# VIC_proto.net
KiCad netlist of a schematic drawn in EAGLE
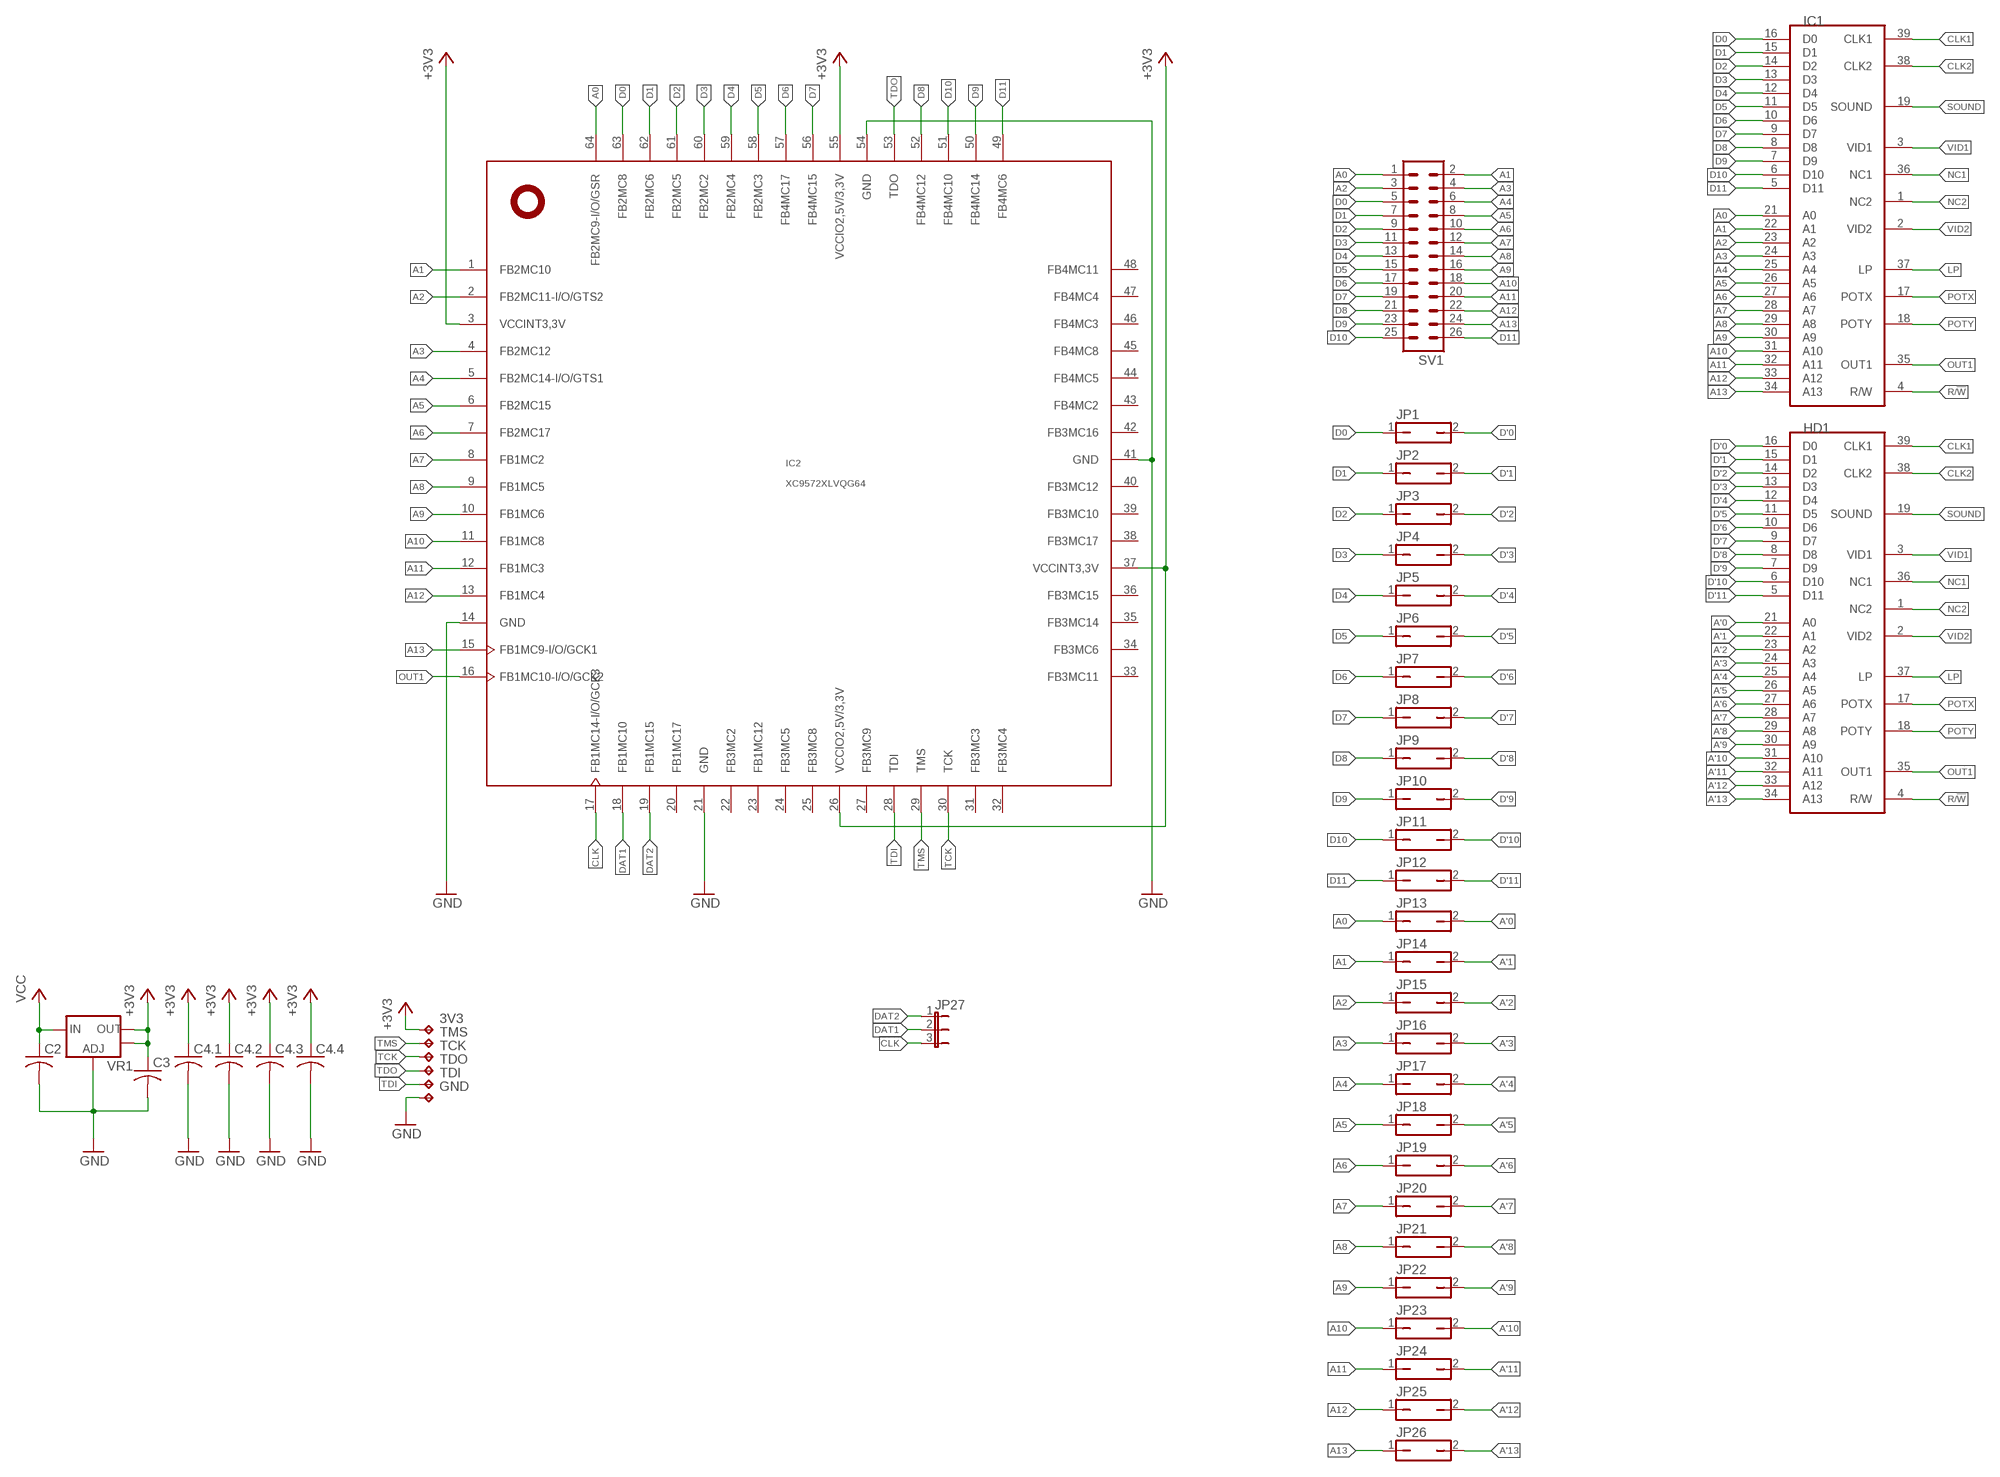
[diagram p0: schematic, sheet 1]

(export (version "E")
  (design (tool "Eeschema 10.0.6"))
  (components
    (comp (ref "3V3")
      (value "TPTP09R")
      (footprint "eagle-import:TP09R")
      (libsource (lib "eagle-import") (part "TPTP09R"))
    )
    (comp (ref "C2")
      (value "C-USC0805")
      (footprint "eagle-import:C0805")
      (libsource (lib "eagle-import") (part "C-USC0805"))
    )
    (comp (ref "C3")
      (value "C-USC0805")
      (footprint "eagle-import:C0805")
      (libsource (lib "eagle-import") (part "C-USC0805"))
    )
    (comp (ref "C4.1")
      (value "C-USC0402")
      (footprint "eagle-import:C0402")
      (libsource (lib "eagle-import") (part "C-USC0402"))
    )
    (comp (ref "C4.2")
      (value "C-USC0402")
      (footprint "eagle-import:C0402")
      (libsource (lib "eagle-import") (part "C-USC0402"))
    )
    (comp (ref "C4.3")
      (value "C-USC0402")
      (footprint "eagle-import:C0402")
      (libsource (lib "eagle-import") (part "C-USC0402"))
    )
    (comp (ref "C4.4")
      (value "C-USC0402")
      (footprint "eagle-import:C0402")
      (libsource (lib "eagle-import") (part "C-USC0402"))
    )
    (comp (ref "GND")
      (value "TPTP10R")
      (footprint "eagle-import:TP10R")
      (libsource (lib "eagle-import") (part "TPTP10R"))
    )
    (comp (ref "HD1")
      (value "6560-RP")
      (footprint "eagle-import:DIL40-ROUNDPAD")
      (libsource (lib "eagle-import") (part "6560-RP"))
    )
    (comp (ref "IC1")
      (value "6560-RP")
      (footprint "eagle-import:DIL40-ROUNDPAD")
      (libsource (lib "eagle-import") (part "6560-RP"))
    )
    (comp (ref "IC2")
      (value "XC9572XLVQG64")
      (footprint "eagle-import:VQFP64")
      (libsource (lib "eagle-import") (part "XC9572XLVQG64"))
    )
    (comp (ref "JP1")
      (value "JP1Q")
      (footprint "eagle-import:JP1")
      (libsource (lib "eagle-import") (part "JP1Q"))
    )
    (comp (ref "JP2")
      (value "JP1Q")
      (footprint "eagle-import:JP1")
      (libsource (lib "eagle-import") (part "JP1Q"))
    )
    (comp (ref "JP3")
      (value "JP1Q")
      (footprint "eagle-import:JP1")
      (libsource (lib "eagle-import") (part "JP1Q"))
    )
    (comp (ref "JP4")
      (value "JP1Q")
      (footprint "eagle-import:JP1")
      (libsource (lib "eagle-import") (part "JP1Q"))
    )
    (comp (ref "JP5")
      (value "JP1Q")
      (footprint "eagle-import:JP1")
      (libsource (lib "eagle-import") (part "JP1Q"))
    )
    (comp (ref "JP6")
      (value "JP1Q")
      (footprint "eagle-import:JP1")
      (libsource (lib "eagle-import") (part "JP1Q"))
    )
    (comp (ref "JP7")
      (value "JP1Q")
      (footprint "eagle-import:JP1")
      (libsource (lib "eagle-import") (part "JP1Q"))
    )
    (comp (ref "JP8")
      (value "JP1Q")
      (footprint "eagle-import:JP1")
      (libsource (lib "eagle-import") (part "JP1Q"))
    )
    (comp (ref "JP9")
      (value "JP1Q")
      (footprint "eagle-import:JP1")
      (libsource (lib "eagle-import") (part "JP1Q"))
    )
    (comp (ref "JP10")
      (value "JP1Q")
      (footprint "eagle-import:JP1")
      (libsource (lib "eagle-import") (part "JP1Q"))
    )
    (comp (ref "JP11")
      (value "JP1Q")
      (footprint "eagle-import:JP1")
      (libsource (lib "eagle-import") (part "JP1Q"))
    )
    (comp (ref "JP12")
      (value "JP1Q")
      (footprint "eagle-import:JP1")
      (libsource (lib "eagle-import") (part "JP1Q"))
    )
    (comp (ref "JP13")
      (value "JP1Q")
      (footprint "eagle-import:JP1")
      (libsource (lib "eagle-import") (part "JP1Q"))
    )
    (comp (ref "JP14")
      (value "JP1Q")
      (footprint "eagle-import:JP1")
      (libsource (lib "eagle-import") (part "JP1Q"))
    )
    (comp (ref "JP15")
      (value "JP1Q")
      (footprint "eagle-import:JP1")
      (libsource (lib "eagle-import") (part "JP1Q"))
    )
    (comp (ref "JP16")
      (value "JP1Q")
      (footprint "eagle-import:JP1")
      (libsource (lib "eagle-import") (part "JP1Q"))
    )
    (comp (ref "JP17")
      (value "JP1Q")
      (footprint "eagle-import:JP1")
      (libsource (lib "eagle-import") (part "JP1Q"))
    )
    (comp (ref "JP18")
      (value "JP1Q")
      (footprint "eagle-import:JP1")
      (libsource (lib "eagle-import") (part "JP1Q"))
    )
    (comp (ref "JP19")
      (value "JP1Q")
      (footprint "eagle-import:JP1")
      (libsource (lib "eagle-import") (part "JP1Q"))
    )
    (comp (ref "JP20")
      (value "JP1Q")
      (footprint "eagle-import:JP1")
      (libsource (lib "eagle-import") (part "JP1Q"))
    )
    (comp (ref "JP21")
      (value "JP1Q")
      (footprint "eagle-import:JP1")
      (libsource (lib "eagle-import") (part "JP1Q"))
    )
    (comp (ref "JP22")
      (value "JP1Q")
      (footprint "eagle-import:JP1")
      (libsource (lib "eagle-import") (part "JP1Q"))
    )
    (comp (ref "JP23")
      (value "JP1Q")
      (footprint "eagle-import:JP1")
      (libsource (lib "eagle-import") (part "JP1Q"))
    )
    (comp (ref "JP24")
      (value "JP1Q")
      (footprint "eagle-import:JP1")
      (libsource (lib "eagle-import") (part "JP1Q"))
    )
    (comp (ref "JP25")
      (value "JP1Q")
      (footprint "eagle-import:JP1")
      (libsource (lib "eagle-import") (part "JP1Q"))
    )
    (comp (ref "JP26")
      (value "JP1Q")
      (footprint "eagle-import:JP1")
      (libsource (lib "eagle-import") (part "JP1Q"))
    )
    (comp (ref "JP27")
      (value "JP2E")
      (footprint "eagle-import:JP2")
      (libsource (lib "eagle-import") (part "JP2E"))
    )
    (comp (ref "SV1")
      (value "MA13-2")
      (footprint "eagle-import:MA13-2")
      (libsource (lib "eagle-import") (part "MA13-2"))
    )
    (comp (ref "TCK")
      (value "TPTP09R")
      (footprint "eagle-import:TP09R")
      (libsource (lib "eagle-import") (part "TPTP09R"))
    )
    (comp (ref "TDI")
      (value "TPTP09R")
      (footprint "eagle-import:TP09R")
      (libsource (lib "eagle-import") (part "TPTP09R"))
    )
    (comp (ref "TDO")
      (value "TPTP09R")
      (footprint "eagle-import:TP09R")
      (libsource (lib "eagle-import") (part "TPTP09R"))
    )
    (comp (ref "TMS")
      (value "TPTP09R")
      (footprint "eagle-import:TP09R")
      (libsource (lib "eagle-import") (part "TPTP09R"))
    )
    (comp (ref "VR1")
      (value "V_REG_LM1117SOT223")
      (footprint "eagle-import:SOT223")
      (libsource (lib "eagle-import") (part "V_REG_LM1117SOT223"))
    )
  )
  (nets
    (net (code "1") (name "+3V3") (class "Default")
      (node (ref "3V3") (pin "TP") (pinfunction "TP_TP") (pintype "input"))
      (node (ref "C3") (pin "1") (pinfunction "1_1") (pintype "passive"))
      (node (ref "C4.1") (pin "1") (pinfunction "1_1") (pintype "passive"))
      (node (ref "C4.2") (pin "1") (pinfunction "1_1") (pintype "passive"))
      (node (ref "C4.3") (pin "1") (pinfunction "1_1") (pintype "passive"))
      (node (ref "C4.4") (pin "1") (pinfunction "1_1") (pintype "passive"))
      (node (ref "IC2") (pin "26") (pinfunction "VCCIO2,5V/3,3V_26") (pintype "power_in"))
      (node (ref "IC2") (pin "3") (pinfunction "VCCINT3,3V_3") (pintype "power_in"))
      (node (ref "IC2") (pin "37") (pinfunction "VCCINT3,3V_37") (pintype "power_in"))
      (node (ref "IC2") (pin "55") (pinfunction "VCCIO2,5V/3,3V_55") (pintype "power_in"))
      (node (ref "VR1") (pin "2") (pinfunction "OUT_2") (pintype "output"))
      (node (ref "VR1") (pin "4") (pinfunction "OUT_4") (pintype "output"))
    )
    (net (code "2") (name "/R{slash}~{W}") (class "Default")
      (node (ref "HD1") (pin "4") (pinfunction "R/W_4") (pintype "input"))
      (node (ref "IC1") (pin "4") (pinfunction "R/W_4") (pintype "input"))
    )
    (net (code "3") (name "A'0") (class "Default")
      (node (ref "HD1") (pin "21") (pinfunction "A0_21") (pintype "bidirectional"))
      (node (ref "JP13") (pin "2") (pinfunction "2_2") (pintype "passive"))
    )
    (net (code "4") (name "A'1") (class "Default")
      (node (ref "HD1") (pin "22") (pinfunction "A1_22") (pintype "bidirectional"))
      (node (ref "JP14") (pin "2") (pinfunction "2_2") (pintype "passive"))
    )
    (net (code "5") (name "A'2") (class "Default")
      (node (ref "HD1") (pin "23") (pinfunction "A2_23") (pintype "bidirectional"))
      (node (ref "JP15") (pin "2") (pinfunction "2_2") (pintype "passive"))
    )
    (net (code "6") (name "A'3") (class "Default")
      (node (ref "HD1") (pin "24") (pinfunction "A3_24") (pintype "bidirectional"))
      (node (ref "JP16") (pin "2") (pinfunction "2_2") (pintype "passive"))
    )
    (net (code "7") (name "A'4") (class "Default")
      (node (ref "HD1") (pin "25") (pinfunction "A4_25") (pintype "bidirectional"))
      (node (ref "JP17") (pin "2") (pinfunction "2_2") (pintype "passive"))
    )
    (net (code "8") (name "A'5") (class "Default")
      (node (ref "HD1") (pin "26") (pinfunction "A5_26") (pintype "bidirectional"))
      (node (ref "JP18") (pin "2") (pinfunction "2_2") (pintype "passive"))
    )
    (net (code "9") (name "A'6") (class "Default")
      (node (ref "HD1") (pin "27") (pinfunction "A6_27") (pintype "bidirectional"))
      (node (ref "JP19") (pin "2") (pinfunction "2_2") (pintype "passive"))
    )
    (net (code "10") (name "A'7") (class "Default")
      (node (ref "HD1") (pin "28") (pinfunction "A7_28") (pintype "bidirectional"))
      (node (ref "JP20") (pin "2") (pinfunction "2_2") (pintype "passive"))
    )
    (net (code "11") (name "A'8") (class "Default")
      (node (ref "HD1") (pin "29") (pinfunction "A8_29") (pintype "bidirectional"))
      (node (ref "JP21") (pin "2") (pinfunction "2_2") (pintype "passive"))
    )
    (net (code "12") (name "A'9") (class "Default")
      (node (ref "HD1") (pin "30") (pinfunction "A9_30") (pintype "bidirectional"))
      (node (ref "JP22") (pin "2") (pinfunction "2_2") (pintype "passive"))
    )
    (net (code "13") (name "A'10") (class "Default")
      (node (ref "HD1") (pin "31") (pinfunction "A10_31") (pintype "bidirectional"))
      (node (ref "JP23") (pin "2") (pinfunction "2_2") (pintype "passive"))
    )
    (net (code "14") (name "A'11") (class "Default")
      (node (ref "HD1") (pin "32") (pinfunction "A11_32") (pintype "bidirectional"))
      (node (ref "JP24") (pin "2") (pinfunction "2_2") (pintype "passive"))
    )
    (net (code "15") (name "A'12") (class "Default")
      (node (ref "HD1") (pin "33") (pinfunction "A12_33") (pintype "bidirectional"))
      (node (ref "JP25") (pin "2") (pinfunction "2_2") (pintype "passive"))
    )
    (net (code "16") (name "A'13") (class "Default")
      (node (ref "HD1") (pin "34") (pinfunction "A13_34") (pintype "bidirectional"))
      (node (ref "JP26") (pin "2") (pinfunction "2_2") (pintype "passive"))
    )
    (net (code "17") (name "A0") (class "Default")
      (node (ref "IC1") (pin "21") (pinfunction "A0_21") (pintype "bidirectional"))
      (node (ref "IC2") (pin "64") (pinfunction "FB2MC9-I/O/GSR_64") (pintype "bidirectional"))
      (node (ref "JP13") (pin "1") (pinfunction "1_1") (pintype "passive"))
      (node (ref "SV1") (pin "1") (pinfunction "1_1") (pintype "passive"))
    )
    (net (code "18") (name "A1") (class "Default")
      (node (ref "IC1") (pin "22") (pinfunction "A1_22") (pintype "bidirectional"))
      (node (ref "IC2") (pin "1") (pinfunction "FB2MC10_1") (pintype "bidirectional"))
      (node (ref "JP14") (pin "1") (pinfunction "1_1") (pintype "passive"))
      (node (ref "SV1") (pin "2") (pinfunction "2_2") (pintype "passive"))
    )
    (net (code "19") (name "A2") (class "Default")
      (node (ref "IC1") (pin "23") (pinfunction "A2_23") (pintype "bidirectional"))
      (node (ref "IC2") (pin "2") (pinfunction "FB2MC11-I/O/GTS2_2") (pintype "bidirectional"))
      (node (ref "JP15") (pin "1") (pinfunction "1_1") (pintype "passive"))
      (node (ref "SV1") (pin "3") (pinfunction "3_3") (pintype "passive"))
    )
    (net (code "20") (name "A3") (class "Default")
      (node (ref "IC1") (pin "24") (pinfunction "A3_24") (pintype "bidirectional"))
      (node (ref "IC2") (pin "4") (pinfunction "FB2MC12_4") (pintype "bidirectional"))
      (node (ref "JP16") (pin "1") (pinfunction "1_1") (pintype "passive"))
      (node (ref "SV1") (pin "4") (pinfunction "4_4") (pintype "passive"))
    )
    (net (code "21") (name "A4") (class "Default")
      (node (ref "IC1") (pin "25") (pinfunction "A4_25") (pintype "bidirectional"))
      (node (ref "IC2") (pin "5") (pinfunction "FB2MC14-I/O/GTS1_5") (pintype "bidirectional"))
      (node (ref "JP17") (pin "1") (pinfunction "1_1") (pintype "passive"))
      (node (ref "SV1") (pin "6") (pinfunction "6_6") (pintype "passive"))
    )
    (net (code "22") (name "A5") (class "Default")
      (node (ref "IC1") (pin "26") (pinfunction "A5_26") (pintype "bidirectional"))
      (node (ref "IC2") (pin "6") (pinfunction "FB2MC15_6") (pintype "bidirectional"))
      (node (ref "JP18") (pin "1") (pinfunction "1_1") (pintype "passive"))
      (node (ref "SV1") (pin "8") (pinfunction "8_8") (pintype "passive"))
    )
    (net (code "23") (name "A6") (class "Default")
      (node (ref "IC1") (pin "27") (pinfunction "A6_27") (pintype "bidirectional"))
      (node (ref "IC2") (pin "7") (pinfunction "FB2MC17_7") (pintype "bidirectional"))
      (node (ref "JP19") (pin "1") (pinfunction "1_1") (pintype "passive"))
      (node (ref "SV1") (pin "10") (pinfunction "10_10") (pintype "passive"))
    )
    (net (code "24") (name "A7") (class "Default")
      (node (ref "IC1") (pin "28") (pinfunction "A7_28") (pintype "bidirectional"))
      (node (ref "IC2") (pin "8") (pinfunction "FB1MC2_8") (pintype "bidirectional"))
      (node (ref "JP20") (pin "1") (pinfunction "1_1") (pintype "passive"))
      (node (ref "SV1") (pin "12") (pinfunction "12_12") (pintype "passive"))
    )
    (net (code "25") (name "A8") (class "Default")
      (node (ref "IC1") (pin "29") (pinfunction "A8_29") (pintype "bidirectional"))
      (node (ref "IC2") (pin "9") (pinfunction "FB1MC5_9") (pintype "bidirectional"))
      (node (ref "JP21") (pin "1") (pinfunction "1_1") (pintype "passive"))
      (node (ref "SV1") (pin "14") (pinfunction "14_14") (pintype "passive"))
    )
    (net (code "26") (name "A9") (class "Default")
      (node (ref "IC1") (pin "30") (pinfunction "A9_30") (pintype "bidirectional"))
      (node (ref "IC2") (pin "10") (pinfunction "FB1MC6_10") (pintype "bidirectional"))
      (node (ref "JP22") (pin "1") (pinfunction "1_1") (pintype "passive"))
      (node (ref "SV1") (pin "16") (pinfunction "16_16") (pintype "passive"))
    )
    (net (code "27") (name "A10") (class "Default")
      (node (ref "IC1") (pin "31") (pinfunction "A10_31") (pintype "bidirectional"))
      (node (ref "IC2") (pin "11") (pinfunction "FB1MC8_11") (pintype "bidirectional"))
      (node (ref "JP23") (pin "1") (pinfunction "1_1") (pintype "passive"))
      (node (ref "SV1") (pin "18") (pinfunction "18_18") (pintype "passive"))
    )
    (net (code "28") (name "A11") (class "Default")
      (node (ref "IC1") (pin "32") (pinfunction "A11_32") (pintype "bidirectional"))
      (node (ref "IC2") (pin "12") (pinfunction "FB1MC3_12") (pintype "bidirectional"))
      (node (ref "JP24") (pin "1") (pinfunction "1_1") (pintype "passive"))
      (node (ref "SV1") (pin "20") (pinfunction "20_20") (pintype "passive"))
    )
    (net (code "29") (name "A12") (class "Default")
      (node (ref "IC1") (pin "33") (pinfunction "A12_33") (pintype "bidirectional"))
      (node (ref "IC2") (pin "13") (pinfunction "FB1MC4_13") (pintype "bidirectional"))
      (node (ref "JP25") (pin "1") (pinfunction "1_1") (pintype "passive"))
      (node (ref "SV1") (pin "22") (pinfunction "22_22") (pintype "passive"))
    )
    (net (code "30") (name "A13") (class "Default")
      (node (ref "IC1") (pin "34") (pinfunction "A13_34") (pintype "bidirectional"))
      (node (ref "IC2") (pin "15") (pinfunction "FB1MC9-I/O/GCK1_15") (pintype "bidirectional"))
      (node (ref "JP26") (pin "1") (pinfunction "1_1") (pintype "passive"))
      (node (ref "SV1") (pin "24") (pinfunction "24_24") (pintype "passive"))
    )
    (net (code "31") (name "CLK") (class "Default")
      (node (ref "IC2") (pin "17") (pinfunction "FB1MC14-I/O/GCK3_17") (pintype "bidirectional"))
      (node (ref "JP27") (pin "3") (pinfunction "3_3") (pintype "passive"))
    )
    (net (code "32") (name "CLK1") (class "Default")
      (node (ref "HD1") (pin "39") (pinfunction "CLK1_39") (pintype "input"))
      (node (ref "IC1") (pin "39") (pinfunction "CLK1_39") (pintype "input"))
    )
    (net (code "33") (name "CLK2") (class "Default")
      (node (ref "HD1") (pin "38") (pinfunction "CLK2_38") (pintype "input"))
      (node (ref "IC1") (pin "38") (pinfunction "CLK2_38") (pintype "input"))
    )
    (net (code "34") (name "D'0") (class "Default")
      (node (ref "HD1") (pin "16") (pinfunction "D0_16") (pintype "tri_state"))
      (node (ref "JP1") (pin "2") (pinfunction "2_2") (pintype "passive"))
    )
    (net (code "35") (name "D'1") (class "Default")
      (node (ref "HD1") (pin "15") (pinfunction "D1_15") (pintype "tri_state"))
      (node (ref "JP2") (pin "2") (pinfunction "2_2") (pintype "passive"))
    )
    (net (code "36") (name "D'2") (class "Default")
      (node (ref "HD1") (pin "14") (pinfunction "D2_14") (pintype "tri_state"))
      (node (ref "JP3") (pin "2") (pinfunction "2_2") (pintype "passive"))
    )
    (net (code "37") (name "D'3") (class "Default")
      (node (ref "HD1") (pin "13") (pinfunction "D3_13") (pintype "tri_state"))
      (node (ref "JP4") (pin "2") (pinfunction "2_2") (pintype "passive"))
    )
    (net (code "38") (name "D'4") (class "Default")
      (node (ref "HD1") (pin "12") (pinfunction "D4_12") (pintype "tri_state"))
      (node (ref "JP5") (pin "2") (pinfunction "2_2") (pintype "passive"))
    )
    (net (code "39") (name "D'5") (class "Default")
      (node (ref "HD1") (pin "11") (pinfunction "D5_11") (pintype "tri_state"))
      (node (ref "JP6") (pin "2") (pinfunction "2_2") (pintype "passive"))
    )
    (net (code "40") (name "D'6") (class "Default")
      (node (ref "HD1") (pin "10") (pinfunction "D6_10") (pintype "tri_state"))
      (node (ref "JP7") (pin "2") (pinfunction "2_2") (pintype "passive"))
    )
    (net (code "41") (name "D'7") (class "Default")
      (node (ref "HD1") (pin "9") (pinfunction "D7_9") (pintype "tri_state"))
      (node (ref "JP8") (pin "2") (pinfunction "2_2") (pintype "passive"))
    )
    (net (code "42") (name "D'8") (class "Default")
      (node (ref "HD1") (pin "8") (pinfunction "D8_8") (pintype "tri_state"))
      (node (ref "JP9") (pin "2") (pinfunction "2_2") (pintype "passive"))
    )
    (net (code "43") (name "D'9") (class "Default")
      (node (ref "HD1") (pin "7") (pinfunction "D9_7") (pintype "tri_state"))
      (node (ref "JP10") (pin "2") (pinfunction "2_2") (pintype "passive"))
    )
    (net (code "44") (name "D'10") (class "Default")
      (node (ref "HD1") (pin "6") (pinfunction "D10_6") (pintype "tri_state"))
      (node (ref "JP11") (pin "2") (pinfunction "2_2") (pintype "passive"))
    )
    (net (code "45") (name "D'11") (class "Default")
      (node (ref "HD1") (pin "5") (pinfunction "D11_5") (pintype "tri_state"))
      (node (ref "JP12") (pin "2") (pinfunction "2_2") (pintype "passive"))
    )
    (net (code "46") (name "D0") (class "Default")
      (node (ref "IC1") (pin "16") (pinfunction "D0_16") (pintype "tri_state"))
      (node (ref "IC2") (pin "63") (pinfunction "FB2MC8_63") (pintype "bidirectional"))
      (node (ref "JP1") (pin "1") (pinfunction "1_1") (pintype "passive"))
      (node (ref "SV1") (pin "5") (pinfunction "5_5") (pintype "passive"))
    )
    (net (code "47") (name "D1") (class "Default")
      (node (ref "IC1") (pin "15") (pinfunction "D1_15") (pintype "tri_state"))
      (node (ref "IC2") (pin "62") (pinfunction "FB2MC6_62") (pintype "bidirectional"))
      (node (ref "JP2") (pin "1") (pinfunction "1_1") (pintype "passive"))
      (node (ref "SV1") (pin "7") (pinfunction "7_7") (pintype "passive"))
    )
    (net (code "48") (name "D2") (class "Default")
      (node (ref "IC1") (pin "14") (pinfunction "D2_14") (pintype "tri_state"))
      (node (ref "IC2") (pin "61") (pinfunction "FB2MC5_61") (pintype "bidirectional"))
      (node (ref "JP3") (pin "1") (pinfunction "1_1") (pintype "passive"))
      (node (ref "SV1") (pin "9") (pinfunction "9_9") (pintype "passive"))
    )
    (net (code "49") (name "D3") (class "Default")
      (node (ref "IC1") (pin "13") (pinfunction "D3_13") (pintype "tri_state"))
      (node (ref "IC2") (pin "60") (pinfunction "FB2MC2_60") (pintype "bidirectional"))
      (node (ref "JP4") (pin "1") (pinfunction "1_1") (pintype "passive"))
      (node (ref "SV1") (pin "11") (pinfunction "11_11") (pintype "passive"))
    )
    (net (code "50") (name "D4") (class "Default")
      (node (ref "IC1") (pin "12") (pinfunction "D4_12") (pintype "tri_state"))
      (node (ref "IC2") (pin "59") (pinfunction "FB2MC4_59") (pintype "bidirectional"))
      (node (ref "JP5") (pin "1") (pinfunction "1_1") (pintype "passive"))
      (node (ref "SV1") (pin "13") (pinfunction "13_13") (pintype "passive"))
    )
    (net (code "51") (name "D5") (class "Default")
      (node (ref "IC1") (pin "11") (pinfunction "D5_11") (pintype "tri_state"))
      (node (ref "IC2") (pin "58") (pinfunction "FB2MC3_58") (pintype "bidirectional"))
      (node (ref "JP6") (pin "1") (pinfunction "1_1") (pintype "passive"))
      (node (ref "SV1") (pin "15") (pinfunction "15_15") (pintype "passive"))
    )
    (net (code "52") (name "D6") (class "Default")
      (node (ref "IC1") (pin "10") (pinfunction "D6_10") (pintype "tri_state"))
      (node (ref "IC2") (pin "57") (pinfunction "FB4MC17_57") (pintype "bidirectional"))
      (node (ref "JP7") (pin "1") (pinfunction "1_1") (pintype "passive"))
      (node (ref "SV1") (pin "17") (pinfunction "17_17") (pintype "passive"))
    )
    (net (code "53") (name "D7") (class "Default")
      (node (ref "IC1") (pin "9") (pinfunction "D7_9") (pintype "tri_state"))
      (node (ref "IC2") (pin "56") (pinfunction "FB4MC15_56") (pintype "bidirectional"))
      (node (ref "JP8") (pin "1") (pinfunction "1_1") (pintype "passive"))
      (node (ref "SV1") (pin "19") (pinfunction "19_19") (pintype "passive"))
    )
    (net (code "54") (name "D8") (class "Default")
      (node (ref "IC1") (pin "8") (pinfunction "D8_8") (pintype "tri_state"))
      (node (ref "IC2") (pin "52") (pinfunction "FB4MC12_52") (pintype "bidirectional"))
      (node (ref "JP9") (pin "1") (pinfunction "1_1") (pintype "passive"))
      (node (ref "SV1") (pin "21") (pinfunction "21_21") (pintype "passive"))
    )
    (net (code "55") (name "D9") (class "Default")
      (node (ref "IC1") (pin "7") (pinfunction "D9_7") (pintype "tri_state"))
      (node (ref "IC2") (pin "50") (pinfunction "FB4MC14_50") (pintype "bidirectional"))
      (node (ref "JP10") (pin "1") (pinfunction "1_1") (pintype "passive"))
      (node (ref "SV1") (pin "23") (pinfunction "23_23") (pintype "passive"))
    )
    (net (code "56") (name "D10") (class "Default")
      (node (ref "IC1") (pin "6") (pinfunction "D10_6") (pintype "tri_state"))
      (node (ref "IC2") (pin "51") (pinfunction "FB4MC10_51") (pintype "bidirectional"))
      (node (ref "JP11") (pin "1") (pinfunction "1_1") (pintype "passive"))
      (node (ref "SV1") (pin "25") (pinfunction "25_25") (pintype "passive"))
    )
    (net (code "57") (name "D11") (class "Default")
      (node (ref "IC1") (pin "5") (pinfunction "D11_5") (pintype "tri_state"))
      (node (ref "IC2") (pin "49") (pinfunction "FB4MC6_49") (pintype "bidirectional"))
      (node (ref "JP12") (pin "1") (pinfunction "1_1") (pintype "passive"))
      (node (ref "SV1") (pin "26") (pinfunction "26_26") (pintype "passive"))
    )
    (net (code "58") (name "DAT1") (class "Default")
      (node (ref "IC2") (pin "18") (pinfunction "FB1MC10_18") (pintype "bidirectional"))
      (node (ref "JP27") (pin "2") (pinfunction "2_2") (pintype "passive"))
    )
    (net (code "59") (name "DAT2") (class "Default")
      (node (ref "IC2") (pin "19") (pinfunction "FB1MC15_19") (pintype "bidirectional"))
      (node (ref "JP27") (pin "1") (pinfunction "1_1") (pintype "passive"))
    )
    (net (code "60") (name "GND") (class "Default")
      (node (ref "C2") (pin "2") (pinfunction "2_2") (pintype "passive"))
      (node (ref "C3") (pin "2") (pinfunction "2_2") (pintype "passive"))
      (node (ref "C4.1") (pin "2") (pinfunction "2_2") (pintype "passive"))
      (node (ref "C4.2") (pin "2") (pinfunction "2_2") (pintype "passive"))
      (node (ref "C4.3") (pin "2") (pinfunction "2_2") (pintype "passive"))
      (node (ref "C4.4") (pin "2") (pinfunction "2_2") (pintype "passive"))
      (node (ref "GND") (pin "TP") (pinfunction "TP_TP") (pintype "input"))
      (node (ref "IC2") (pin "14") (pinfunction "GND_14") (pintype "power_in"))
      (node (ref "IC2") (pin "21") (pinfunction "GND_21") (pintype "power_in"))
      (node (ref "IC2") (pin "41") (pinfunction "GND_41") (pintype "power_in"))
      (node (ref "IC2") (pin "54") (pinfunction "GND_54") (pintype "power_in"))
      (node (ref "VR1") (pin "1") (pinfunction "ADJ_1") (pintype "input"))
    )
    (net (code "61") (name "LP") (class "Default")
      (node (ref "HD1") (pin "37") (pinfunction "LP_37") (pintype "input"))
      (node (ref "IC1") (pin "37") (pinfunction "LP_37") (pintype "input"))
    )
    (net (code "62") (name "NC1") (class "Default")
      (node (ref "HD1") (pin "36") (pinfunction "NC1_36") (pintype "passive"))
      (node (ref "IC1") (pin "36") (pinfunction "NC1_36") (pintype "passive"))
    )
    (net (code "63") (name "NC2") (class "Default")
      (node (ref "HD1") (pin "1") (pinfunction "NC2_1") (pintype "passive"))
      (node (ref "IC1") (pin "1") (pinfunction "NC2_1") (pintype "passive"))
    )
    (net (code "64") (name "OUT1") (class "Default")
      (node (ref "HD1") (pin "35") (pinfunction "OUT1_35") (pintype "output"))
      (node (ref "IC1") (pin "35") (pinfunction "OUT1_35") (pintype "output"))
      (node (ref "IC2") (pin "16") (pinfunction "FB1MC10-I/O/GCK2_16") (pintype "bidirectional"))
    )
    (net (code "65") (name "POTX") (class "Default")
      (node (ref "HD1") (pin "17") (pinfunction "POTX_17") (pintype "input"))
      (node (ref "IC1") (pin "17") (pinfunction "POTX_17") (pintype "input"))
    )
    (net (code "66") (name "POTY") (class "Default")
      (node (ref "HD1") (pin "18") (pinfunction "POTY_18") (pintype "input"))
      (node (ref "IC1") (pin "18") (pinfunction "POTY_18") (pintype "input"))
    )
    (net (code "67") (name "SOUND") (class "Default")
      (node (ref "HD1") (pin "19") (pinfunction "SOUND_19") (pintype "output"))
      (node (ref "IC1") (pin "19") (pinfunction "SOUND_19") (pintype "output"))
    )
    (net (code "68") (name "TCK") (class "Default")
      (node (ref "IC2") (pin "30") (pinfunction "TCK_30") (pintype "bidirectional"))
      (node (ref "TCK") (pin "TP") (pinfunction "TP_TP") (pintype "input"))
    )
    (net (code "69") (name "TDI") (class "Default")
      (node (ref "IC2") (pin "28") (pinfunction "TDI_28") (pintype "bidirectional"))
      (node (ref "TDI") (pin "TP") (pinfunction "TP_TP") (pintype "input"))
    )
    (net (code "70") (name "TDO") (class "Default")
      (node (ref "IC2") (pin "53") (pinfunction "TDO_53") (pintype "bidirectional"))
      (node (ref "TDO") (pin "TP") (pinfunction "TP_TP") (pintype "input"))
    )
    (net (code "71") (name "TMS") (class "Default")
      (node (ref "IC2") (pin "29") (pinfunction "TMS_29") (pintype "bidirectional"))
      (node (ref "TMS") (pin "TP") (pinfunction "TP_TP") (pintype "input"))
    )
    (net (code "72") (name "VCC") (class "Default")
      (node (ref "C2") (pin "1") (pinfunction "1_1") (pintype "passive"))
      (node (ref "VR1") (pin "3") (pinfunction "IN_3") (pintype "input"))
    )
    (net (code "73") (name "VID1") (class "Default")
      (node (ref "HD1") (pin "3") (pinfunction "VID1_3") (pintype "output"))
      (node (ref "IC1") (pin "3") (pinfunction "VID1_3") (pintype "output"))
    )
    (net (code "74") (name "VID2") (class "Default")
      (node (ref "HD1") (pin "2") (pinfunction "VID2_2") (pintype "output"))
      (node (ref "IC1") (pin "2") (pinfunction "VID2_2") (pintype "output"))
    )
    (net (code "75") (name "unconnected-(IC2-FB1MC12-Pad23)") (class "Default")
      (node (ref "IC2") (pin "23") (pinfunction "FB1MC12_23") (pintype "bidirectional"))
    )
    (net (code "76") (name "unconnected-(IC2-FB1MC17-Pad20)") (class "Default")
      (node (ref "IC2") (pin "20") (pinfunction "FB1MC17_20") (pintype "bidirectional"))
    )
    (net (code "77") (name "unconnected-(IC2-FB3MC2-Pad22)") (class "Default")
      (node (ref "IC2") (pin "22") (pinfunction "FB3MC2_22") (pintype "bidirectional"))
    )
    (net (code "78") (name "unconnected-(IC2-FB3MC3-Pad31)") (class "Default")
      (node (ref "IC2") (pin "31") (pinfunction "FB3MC3_31") (pintype "bidirectional"))
    )
    (net (code "79") (name "unconnected-(IC2-FB3MC4-Pad32)") (class "Default")
      (node (ref "IC2") (pin "32") (pinfunction "FB3MC4_32") (pintype "bidirectional"))
    )
    (net (code "80") (name "unconnected-(IC2-FB3MC5-Pad24)") (class "Default")
      (node (ref "IC2") (pin "24") (pinfunction "FB3MC5_24") (pintype "bidirectional"))
    )
    (net (code "81") (name "unconnected-(IC2-FB3MC6-Pad34)") (class "Default")
      (node (ref "IC2") (pin "34") (pinfunction "FB3MC6_34") (pintype "bidirectional"))
    )
    (net (code "82") (name "unconnected-(IC2-FB3MC8-Pad25)") (class "Default")
      (node (ref "IC2") (pin "25") (pinfunction "FB3MC8_25") (pintype "bidirectional"))
    )
    (net (code "83") (name "unconnected-(IC2-FB3MC9-Pad27)") (class "Default")
      (node (ref "IC2") (pin "27") (pinfunction "FB3MC9_27") (pintype "bidirectional"))
    )
    (net (code "84") (name "unconnected-(IC2-FB3MC10-Pad39)") (class "Default")
      (node (ref "IC2") (pin "39") (pinfunction "FB3MC10_39") (pintype "bidirectional"))
    )
    (net (code "85") (name "unconnected-(IC2-FB3MC11-Pad33)") (class "Default")
      (node (ref "IC2") (pin "33") (pinfunction "FB3MC11_33") (pintype "bidirectional"))
    )
    (net (code "86") (name "unconnected-(IC2-FB3MC12-Pad40)") (class "Default")
      (node (ref "IC2") (pin "40") (pinfunction "FB3MC12_40") (pintype "bidirectional"))
    )
    (net (code "87") (name "unconnected-(IC2-FB3MC14-Pad35)") (class "Default")
      (node (ref "IC2") (pin "35") (pinfunction "FB3MC14_35") (pintype "bidirectional"))
    )
    (net (code "88") (name "unconnected-(IC2-FB3MC15-Pad36)") (class "Default")
      (node (ref "IC2") (pin "36") (pinfunction "FB3MC15_36") (pintype "bidirectional"))
    )
    (net (code "89") (name "unconnected-(IC2-FB3MC16-Pad42)") (class "Default")
      (node (ref "IC2") (pin "42") (pinfunction "FB3MC16_42") (pintype "bidirectional"))
    )
    (net (code "90") (name "unconnected-(IC2-FB3MC17-Pad38)") (class "Default")
      (node (ref "IC2") (pin "38") (pinfunction "FB3MC17_38") (pintype "bidirectional"))
    )
    (net (code "91") (name "unconnected-(IC2-FB4MC2-Pad43)") (class "Default")
      (node (ref "IC2") (pin "43") (pinfunction "FB4MC2_43") (pintype "bidirectional"))
    )
    (net (code "92") (name "unconnected-(IC2-FB4MC3-Pad46)") (class "Default")
      (node (ref "IC2") (pin "46") (pinfunction "FB4MC3_46") (pintype "bidirectional"))
    )
    (net (code "93") (name "unconnected-(IC2-FB4MC4-Pad47)") (class "Default")
      (node (ref "IC2") (pin "47") (pinfunction "FB4MC4_47") (pintype "bidirectional"))
    )
    (net (code "94") (name "unconnected-(IC2-FB4MC5-Pad44)") (class "Default")
      (node (ref "IC2") (pin "44") (pinfunction "FB4MC5_44") (pintype "bidirectional"))
    )
    (net (code "95") (name "unconnected-(IC2-FB4MC8-Pad45)") (class "Default")
      (node (ref "IC2") (pin "45") (pinfunction "FB4MC8_45") (pintype "bidirectional"))
    )
    (net (code "96") (name "unconnected-(IC2-FB4MC11-Pad48)") (class "Default")
      (node (ref "IC2") (pin "48") (pinfunction "FB4MC11_48") (pintype "bidirectional"))
    )
  )
)
